# Pushbutton_Breakout_-_Schematic.net
KiCad netlist of a schematic drawn in EAGLE
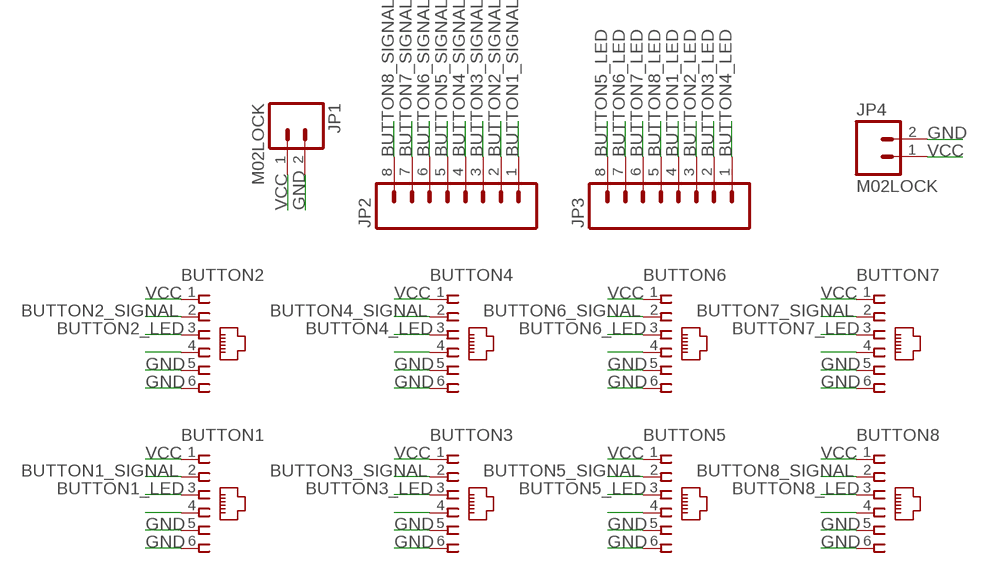
[diagram p0: schematic, sheet 1]

(export (version "E")
  (design (tool "Eeschema 10.0.6"))
  (components
    (comp (ref "BUTTON1")
      (value "555165-1")
      (footprint "eagle-import:555165-1")
      (libsource (lib "eagle-import") (part "555165-1"))
    )
    (comp (ref "BUTTON2")
      (value "555165-1")
      (footprint "eagle-import:555165-1")
      (libsource (lib "eagle-import") (part "555165-1"))
    )
    (comp (ref "BUTTON3")
      (value "555165-1")
      (footprint "eagle-import:555165-1")
      (libsource (lib "eagle-import") (part "555165-1"))
    )
    (comp (ref "BUTTON4")
      (value "555165-1")
      (footprint "eagle-import:555165-1")
      (libsource (lib "eagle-import") (part "555165-1"))
    )
    (comp (ref "BUTTON5")
      (value "555165-1")
      (footprint "eagle-import:555165-1")
      (libsource (lib "eagle-import") (part "555165-1"))
    )
    (comp (ref "BUTTON6")
      (value "555165-1")
      (footprint "eagle-import:555165-1")
      (libsource (lib "eagle-import") (part "555165-1"))
    )
    (comp (ref "BUTTON7")
      (value "555165-1")
      (footprint "eagle-import:555165-1")
      (libsource (lib "eagle-import") (part "555165-1"))
    )
    (comp (ref "BUTTON8")
      (value "555165-1")
      (footprint "eagle-import:555165-1")
      (libsource (lib "eagle-import") (part "555165-1"))
    )
    (comp (ref "JP1")
      (value "M02LOCK")
      (footprint "eagle-import:1X02_LOCK")
      (libsource (lib "eagle-import") (part "M02LOCK"))
    )
    (comp (ref "JP2")
      (value "M08LOCK")
      (footprint "eagle-import:1X08_LOCK")
      (libsource (lib "eagle-import") (part "M08LOCK"))
    )
    (comp (ref "JP3")
      (value "M08LOCK")
      (footprint "eagle-import:1X08_LOCK")
      (libsource (lib "eagle-import") (part "M08LOCK"))
    )
    (comp (ref "JP4")
      (value "M02LOCK")
      (footprint "eagle-import:1X02_LOCK")
      (libsource (lib "eagle-import") (part "M02LOCK"))
    )
  )
  (nets
    (net (code "1") (name "/BUTTON1_LED") (class "Default")
      (node (ref "BUTTON1") (pin "3") (pinfunction "3_3") (pintype "passive"))
      (node (ref "JP3") (pin "4") (pinfunction "4_4") (pintype "passive"))
    )
    (net (code "2") (name "/BUTTON1_SIGNAL") (class "Default")
      (node (ref "BUTTON1") (pin "2") (pinfunction "2_2") (pintype "passive"))
      (node (ref "JP2") (pin "1") (pinfunction "1_1") (pintype "passive"))
    )
    (net (code "3") (name "/BUTTON2_LED") (class "Default")
      (node (ref "BUTTON2") (pin "3") (pinfunction "3_3") (pintype "passive"))
      (node (ref "JP3") (pin "3") (pinfunction "3_3") (pintype "passive"))
    )
    (net (code "4") (name "/BUTTON2_SIGNAL") (class "Default")
      (node (ref "BUTTON2") (pin "2") (pinfunction "2_2") (pintype "passive"))
      (node (ref "JP2") (pin "2") (pinfunction "2_2") (pintype "passive"))
    )
    (net (code "5") (name "/BUTTON3_LED") (class "Default")
      (node (ref "BUTTON3") (pin "3") (pinfunction "3_3") (pintype "passive"))
      (node (ref "JP3") (pin "2") (pinfunction "2_2") (pintype "passive"))
    )
    (net (code "6") (name "/BUTTON3_SIGNAL") (class "Default")
      (node (ref "BUTTON3") (pin "2") (pinfunction "2_2") (pintype "passive"))
      (node (ref "JP2") (pin "3") (pinfunction "3_3") (pintype "passive"))
    )
    (net (code "7") (name "/BUTTON4_LED") (class "Default")
      (node (ref "BUTTON4") (pin "3") (pinfunction "3_3") (pintype "passive"))
      (node (ref "JP3") (pin "1") (pinfunction "1_1") (pintype "passive"))
    )
    (net (code "8") (name "/BUTTON4_SIGNAL") (class "Default")
      (node (ref "BUTTON4") (pin "2") (pinfunction "2_2") (pintype "passive"))
      (node (ref "JP2") (pin "4") (pinfunction "4_4") (pintype "passive"))
    )
    (net (code "9") (name "/BUTTON5_LED") (class "Default")
      (node (ref "BUTTON5") (pin "3") (pinfunction "3_3") (pintype "passive"))
      (node (ref "JP3") (pin "8") (pinfunction "8_8") (pintype "passive"))
    )
    (net (code "10") (name "/BUTTON5_SIGNAL") (class "Default")
      (node (ref "BUTTON5") (pin "2") (pinfunction "2_2") (pintype "passive"))
      (node (ref "JP2") (pin "5") (pinfunction "5_5") (pintype "passive"))
    )
    (net (code "11") (name "/BUTTON6_LED") (class "Default")
      (node (ref "BUTTON6") (pin "3") (pinfunction "3_3") (pintype "passive"))
      (node (ref "JP3") (pin "7") (pinfunction "7_7") (pintype "passive"))
    )
    (net (code "12") (name "/BUTTON6_SIGNAL") (class "Default")
      (node (ref "BUTTON6") (pin "2") (pinfunction "2_2") (pintype "passive"))
      (node (ref "JP2") (pin "6") (pinfunction "6_6") (pintype "passive"))
    )
    (net (code "13") (name "/BUTTON7_LED") (class "Default")
      (node (ref "BUTTON7") (pin "3") (pinfunction "3_3") (pintype "passive"))
      (node (ref "JP3") (pin "6") (pinfunction "6_6") (pintype "passive"))
    )
    (net (code "14") (name "/BUTTON7_SIGNAL") (class "Default")
      (node (ref "BUTTON7") (pin "2") (pinfunction "2_2") (pintype "passive"))
      (node (ref "JP2") (pin "7") (pinfunction "7_7") (pintype "passive"))
    )
    (net (code "15") (name "/BUTTON8_LED") (class "Default")
      (node (ref "BUTTON8") (pin "3") (pinfunction "3_3") (pintype "passive"))
      (node (ref "JP3") (pin "5") (pinfunction "5_5") (pintype "passive"))
    )
    (net (code "16") (name "/BUTTON8_SIGNAL") (class "Default")
      (node (ref "BUTTON8") (pin "2") (pinfunction "2_2") (pintype "passive"))
      (node (ref "JP2") (pin "8") (pinfunction "8_8") (pintype "passive"))
    )
    (net (code "17") (name "/GND") (class "Default")
      (node (ref "BUTTON1") (pin "5") (pinfunction "5_5") (pintype "passive"))
      (node (ref "BUTTON1") (pin "6") (pinfunction "6_6") (pintype "passive"))
      (node (ref "BUTTON2") (pin "5") (pinfunction "5_5") (pintype "passive"))
      (node (ref "BUTTON2") (pin "6") (pinfunction "6_6") (pintype "passive"))
      (node (ref "BUTTON3") (pin "5") (pinfunction "5_5") (pintype "passive"))
      (node (ref "BUTTON3") (pin "6") (pinfunction "6_6") (pintype "passive"))
      (node (ref "BUTTON4") (pin "5") (pinfunction "5_5") (pintype "passive"))
      (node (ref "BUTTON4") (pin "6") (pinfunction "6_6") (pintype "passive"))
      (node (ref "BUTTON5") (pin "5") (pinfunction "5_5") (pintype "passive"))
      (node (ref "BUTTON5") (pin "6") (pinfunction "6_6") (pintype "passive"))
      (node (ref "BUTTON6") (pin "5") (pinfunction "5_5") (pintype "passive"))
      (node (ref "BUTTON6") (pin "6") (pinfunction "6_6") (pintype "passive"))
      (node (ref "BUTTON7") (pin "5") (pinfunction "5_5") (pintype "passive"))
      (node (ref "BUTTON7") (pin "6") (pinfunction "6_6") (pintype "passive"))
      (node (ref "BUTTON8") (pin "5") (pinfunction "5_5") (pintype "passive"))
      (node (ref "BUTTON8") (pin "6") (pinfunction "6_6") (pintype "passive"))
      (node (ref "JP1") (pin "2") (pinfunction "2_2") (pintype "passive"))
      (node (ref "JP4") (pin "2") (pinfunction "2_2") (pintype "passive"))
    )
    (net (code "18") (name "/VCC") (class "Default")
      (node (ref "BUTTON1") (pin "1") (pinfunction "1_1") (pintype "passive"))
      (node (ref "BUTTON2") (pin "1") (pinfunction "1_1") (pintype "passive"))
      (node (ref "BUTTON3") (pin "1") (pinfunction "1_1") (pintype "passive"))
      (node (ref "BUTTON4") (pin "1") (pinfunction "1_1") (pintype "passive"))
      (node (ref "BUTTON5") (pin "1") (pinfunction "1_1") (pintype "passive"))
      (node (ref "BUTTON6") (pin "1") (pinfunction "1_1") (pintype "passive"))
      (node (ref "BUTTON7") (pin "1") (pinfunction "1_1") (pintype "passive"))
      (node (ref "BUTTON8") (pin "1") (pinfunction "1_1") (pintype "passive"))
      (node (ref "JP1") (pin "1") (pinfunction "1_1") (pintype "passive"))
      (node (ref "JP4") (pin "1") (pinfunction "1_1") (pintype "passive"))
    )
    (net (code "19") (name "unconnected-(BUTTON1-Pad4)") (class "Default")
      (node (ref "BUTTON1") (pin "4") (pinfunction "4_4") (pintype "passive"))
    )
    (net (code "20") (name "unconnected-(BUTTON2-Pad4)") (class "Default")
      (node (ref "BUTTON2") (pin "4") (pinfunction "4_4") (pintype "passive"))
    )
    (net (code "21") (name "unconnected-(BUTTON3-Pad4)") (class "Default")
      (node (ref "BUTTON3") (pin "4") (pinfunction "4_4") (pintype "passive"))
    )
    (net (code "22") (name "unconnected-(BUTTON4-Pad4)") (class "Default")
      (node (ref "BUTTON4") (pin "4") (pinfunction "4_4") (pintype "passive"))
    )
    (net (code "23") (name "unconnected-(BUTTON5-Pad4)") (class "Default")
      (node (ref "BUTTON5") (pin "4") (pinfunction "4_4") (pintype "passive"))
    )
    (net (code "24") (name "unconnected-(BUTTON6-Pad4)") (class "Default")
      (node (ref "BUTTON6") (pin "4") (pinfunction "4_4") (pintype "passive"))
    )
    (net (code "25") (name "unconnected-(BUTTON7-Pad4)") (class "Default")
      (node (ref "BUTTON7") (pin "4") (pinfunction "4_4") (pintype "passive"))
    )
    (net (code "26") (name "unconnected-(BUTTON8-Pad4)") (class "Default")
      (node (ref "BUTTON8") (pin "4") (pinfunction "4_4") (pintype "passive"))
    )
  )
)
